# 701_GridPos7.net
KiCad netlist of a schematic drawn in Altium Designer
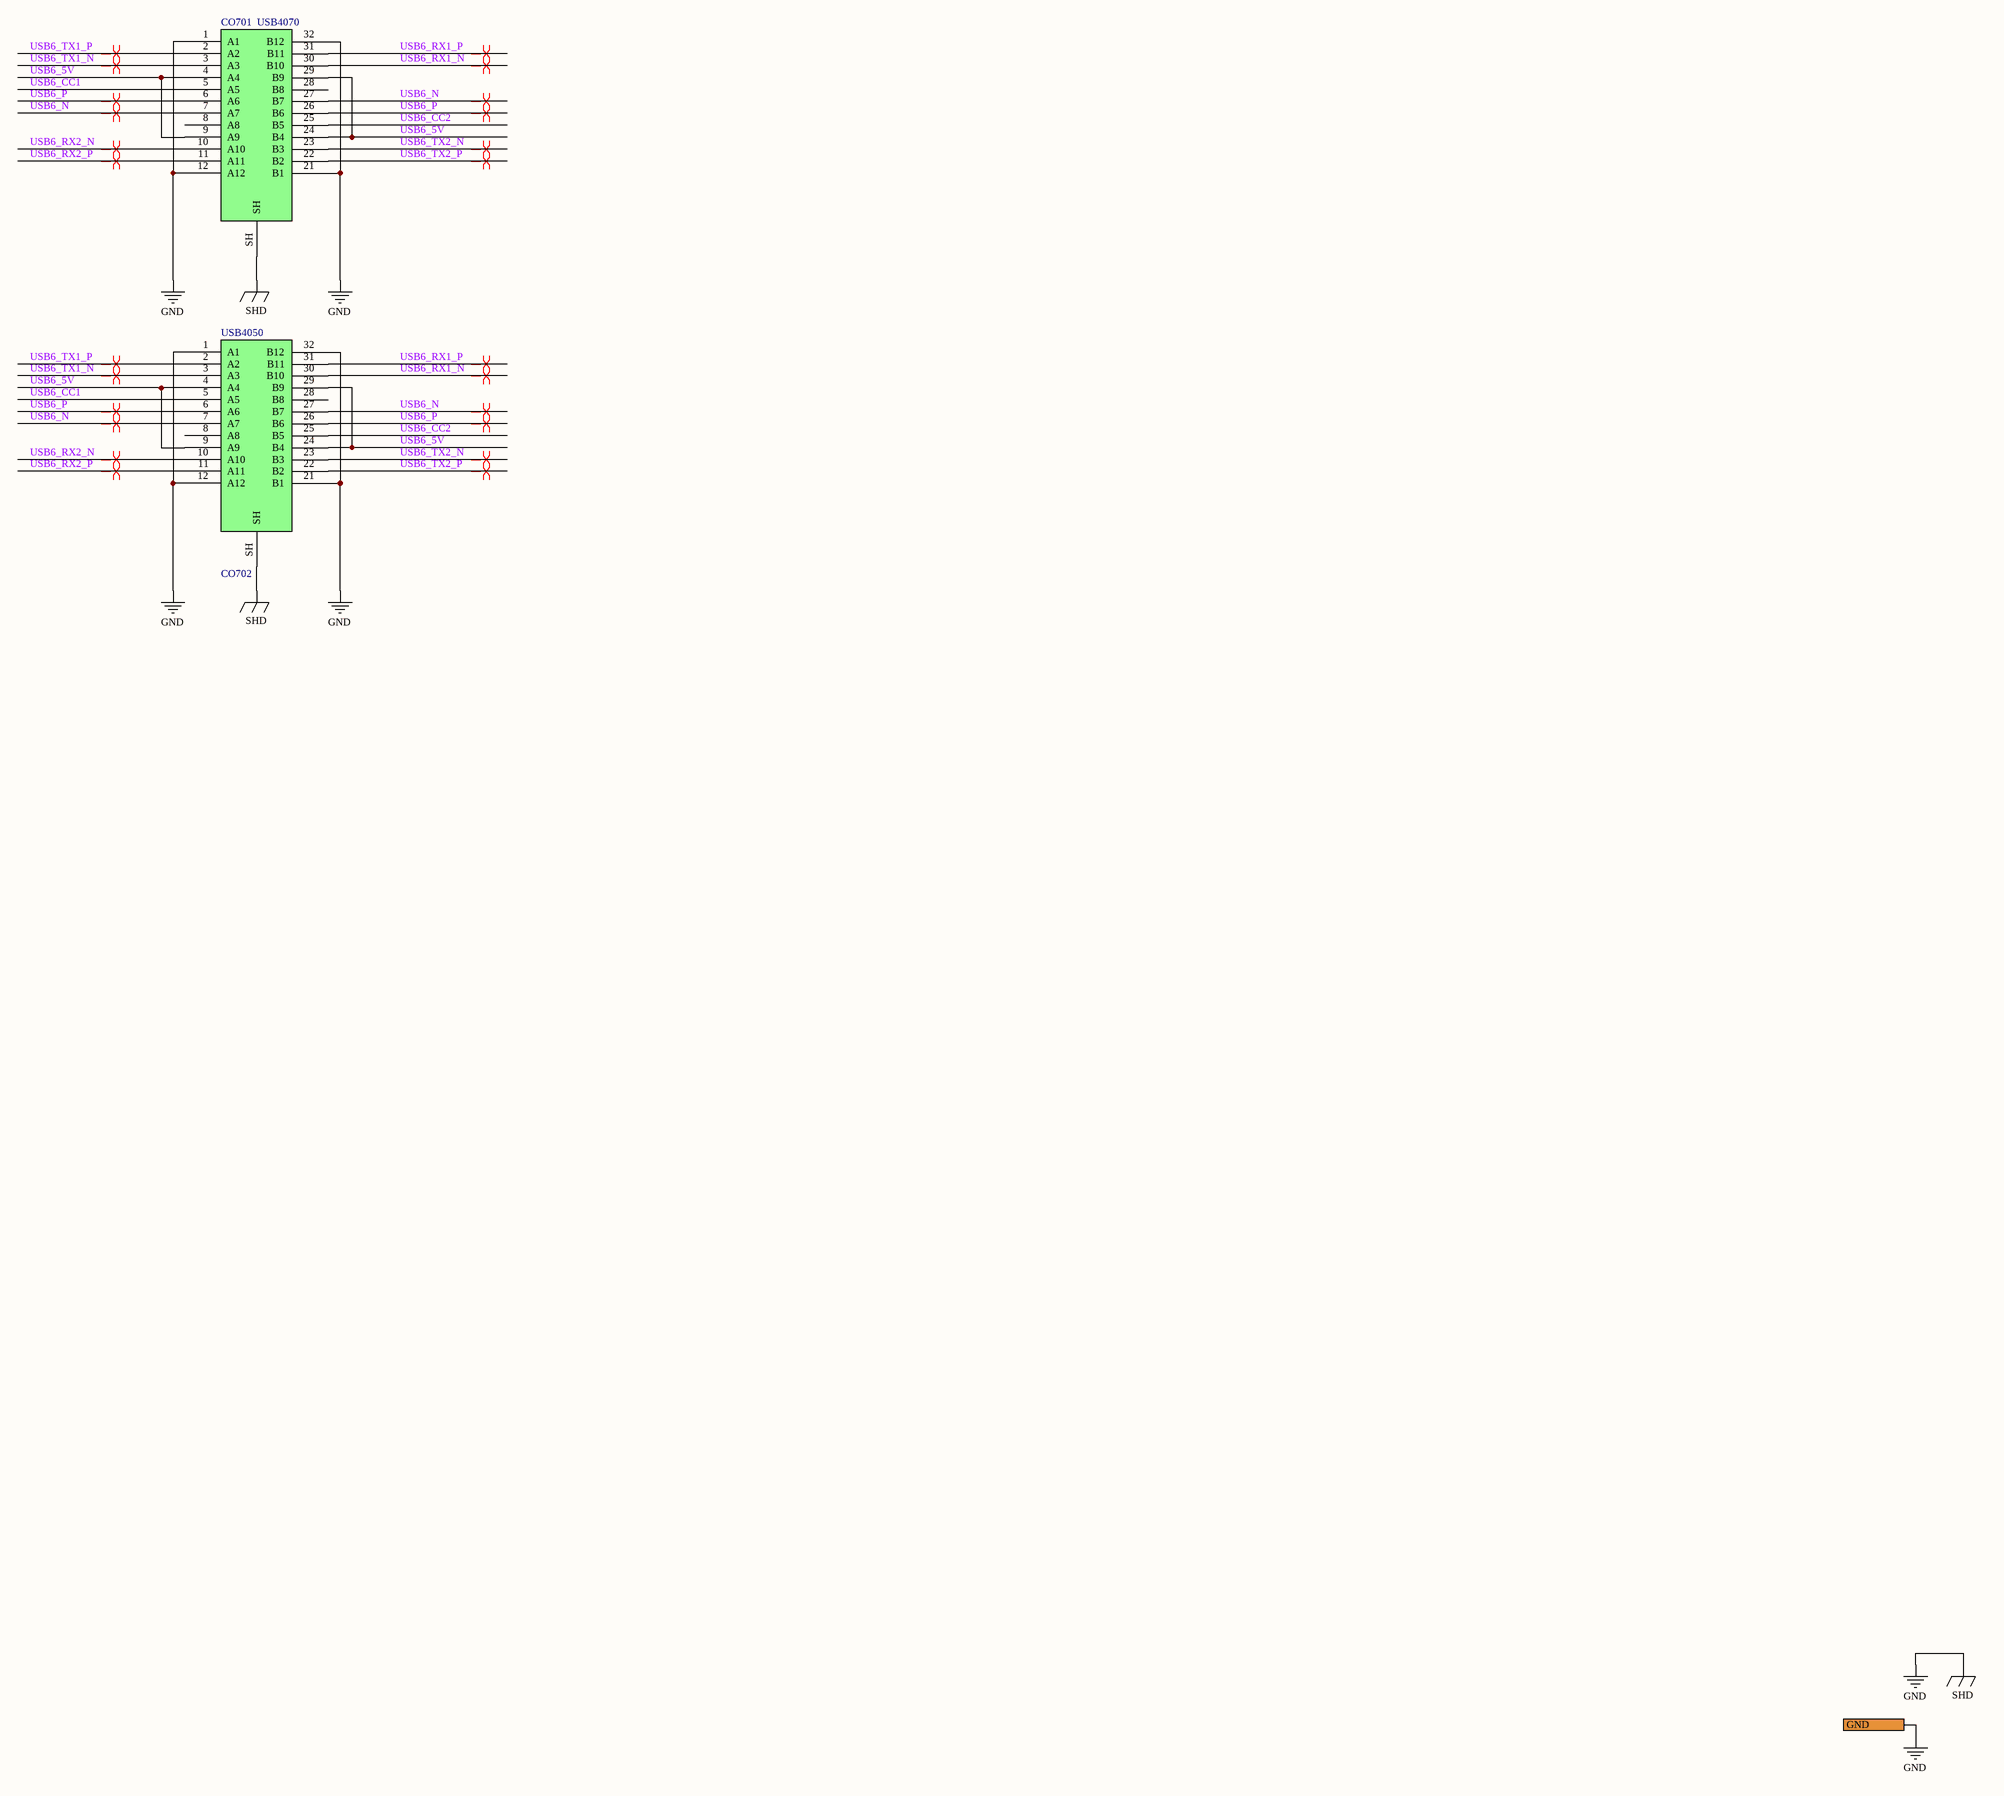
[diagram p0: 701_GridPos7.SchDoc]

(export (version "E")
  (design (tool "Eeschema 10.0.6"))
  (components
    (comp (ref "CO701")
      (value "USB4070")
      (footprint "USB4070-30-C")
      (description "USB4070-30-C")
      (fields (field (name "REFVAL") "USB4070") (field (name "PART NUMBER") "CO0021"))
      (libsource (lib "GTS_Database") (part "USB-CC"))
    )
    (comp (ref "CO702")
      (value "USB4050")
      (footprint "USB4050-30-A")
      (description "USB C connector Receptacle Horizontal")
      (fields
        (field (name "REFVAL") "USB4050")
        (field (name "PART NUMBER") "CO0039")
        (field (name "MANFACTPART") "USB4050-30-A")
      )
      (libsource (lib "") (part "USB-CC_1"))
    )
  )
  (nets
    (net (code "1") (name "/USB6_5V") (class "Default")
      (node (ref "CO701") (pin "24") (pinfunction "B4_24") (pintype "passive"))
      (node (ref "CO701") (pin "29") (pinfunction "B9_29") (pintype "passive"))
      (node (ref "CO701") (pin "4") (pinfunction "A4_4") (pintype "passive"))
      (node (ref "CO701") (pin "9") (pinfunction "A9_9") (pintype "passive"))
      (node (ref "CO702") (pin "24") (pinfunction "B4_24") (pintype "passive"))
      (node (ref "CO702") (pin "29") (pinfunction "B9_29") (pintype "passive"))
      (node (ref "CO702") (pin "4") (pinfunction "A4_4") (pintype "passive"))
      (node (ref "CO702") (pin "9") (pinfunction "A9_9") (pintype "passive"))
    )
    (net (code "2") (name "/USB6_CC1") (class "Default")
      (node (ref "CO701") (pin "5") (pinfunction "A5_5") (pintype "passive"))
      (node (ref "CO702") (pin "5") (pinfunction "A5_5") (pintype "passive"))
    )
    (net (code "3") (name "/USB6_CC2") (class "Default")
      (node (ref "CO701") (pin "25") (pinfunction "B5_25") (pintype "passive"))
      (node (ref "CO702") (pin "25") (pinfunction "B5_25") (pintype "passive"))
    )
    (net (code "4") (name "/USB6_N") (class "Default")
      (node (ref "CO701") (pin "27") (pinfunction "B7_27") (pintype "passive"))
      (node (ref "CO701") (pin "7") (pinfunction "A7_7") (pintype "passive"))
      (node (ref "CO702") (pin "27") (pinfunction "B7_27") (pintype "passive"))
      (node (ref "CO702") (pin "7") (pinfunction "A7_7") (pintype "passive"))
    )
    (net (code "5") (name "/USB6_P") (class "Default")
      (node (ref "CO701") (pin "26") (pinfunction "B6_26") (pintype "passive"))
      (node (ref "CO701") (pin "6") (pinfunction "A6_6") (pintype "passive"))
      (node (ref "CO702") (pin "26") (pinfunction "B6_26") (pintype "passive"))
      (node (ref "CO702") (pin "6") (pinfunction "A6_6") (pintype "passive"))
    )
    (net (code "6") (name "/USB6_RX1_N") (class "Default")
      (node (ref "CO701") (pin "30") (pinfunction "B10_30") (pintype "passive"))
      (node (ref "CO702") (pin "30") (pinfunction "B10_30") (pintype "passive"))
    )
    (net (code "7") (name "/USB6_RX1_P") (class "Default")
      (node (ref "CO701") (pin "31") (pinfunction "B11_31") (pintype "passive"))
      (node (ref "CO702") (pin "31") (pinfunction "B11_31") (pintype "passive"))
    )
    (net (code "8") (name "/USB6_RX2_N") (class "Default")
      (node (ref "CO701") (pin "10") (pinfunction "A10_10") (pintype "passive"))
      (node (ref "CO702") (pin "10") (pinfunction "A10_10") (pintype "passive"))
    )
    (net (code "9") (name "/USB6_RX2_P") (class "Default")
      (node (ref "CO701") (pin "11") (pinfunction "A11_11") (pintype "passive"))
      (node (ref "CO702") (pin "11") (pinfunction "A11_11") (pintype "passive"))
    )
    (net (code "10") (name "/USB6_TX1_N") (class "Default")
      (node (ref "CO701") (pin "3") (pinfunction "A3_3") (pintype "passive"))
      (node (ref "CO702") (pin "3") (pinfunction "A3_3") (pintype "passive"))
    )
    (net (code "11") (name "/USB6_TX1_P") (class "Default")
      (node (ref "CO701") (pin "2") (pinfunction "A2_2") (pintype "passive"))
      (node (ref "CO702") (pin "2") (pinfunction "A2_2") (pintype "passive"))
    )
    (net (code "12") (name "/USB6_TX2_N") (class "Default")
      (node (ref "CO701") (pin "23") (pinfunction "B3_23") (pintype "passive"))
      (node (ref "CO702") (pin "23") (pinfunction "B3_23") (pintype "passive"))
    )
    (net (code "13") (name "/USB6_TX2_P") (class "Default")
      (node (ref "CO701") (pin "22") (pinfunction "B2_22") (pintype "passive"))
      (node (ref "CO702") (pin "22") (pinfunction "B2_22") (pintype "passive"))
    )
    (net (code "14") (name "GND") (class "Default")
      (node (ref "CO701") (pin "1") (pinfunction "A1_1") (pintype "passive"))
      (node (ref "CO701") (pin "12") (pinfunction "A12_12") (pintype "passive"))
      (node (ref "CO701") (pin "21") (pinfunction "B1_21") (pintype "passive"))
      (node (ref "CO701") (pin "32") (pinfunction "B12_32") (pintype "passive"))
      (node (ref "CO701") (pin "SH") (pinfunction "SH_SH") (pintype "power_in"))
      (node (ref "CO702") (pin "1") (pinfunction "A1_1") (pintype "passive"))
      (node (ref "CO702") (pin "12") (pinfunction "A12_12") (pintype "passive"))
      (node (ref "CO702") (pin "21") (pinfunction "B1_21") (pintype "passive"))
      (node (ref "CO702") (pin "32") (pinfunction "B12_32") (pintype "passive"))
      (node (ref "CO702") (pin "SH") (pinfunction "SH_SH") (pintype "power_in"))
    )
    (net (code "15") (name "unconnected-(CO701-A8-Pad8)") (class "Default")
      (node (ref "CO701") (pin "8") (pinfunction "A8_8") (pintype "passive"))
    )
    (net (code "16") (name "unconnected-(CO701-B8-Pad28)") (class "Default")
      (node (ref "CO701") (pin "28") (pinfunction "B8_28") (pintype "passive"))
    )
    (net (code "17") (name "unconnected-(CO702-A8-Pad8)") (class "Default")
      (node (ref "CO702") (pin "8") (pinfunction "A8_8") (pintype "passive"))
    )
    (net (code "18") (name "unconnected-(CO702-B8-Pad28)") (class "Default")
      (node (ref "CO702") (pin "28") (pinfunction "B8_28") (pintype "passive"))
    )
  )
)
